# MCU.net
KiCad netlist of a schematic drawn in Altium Designer
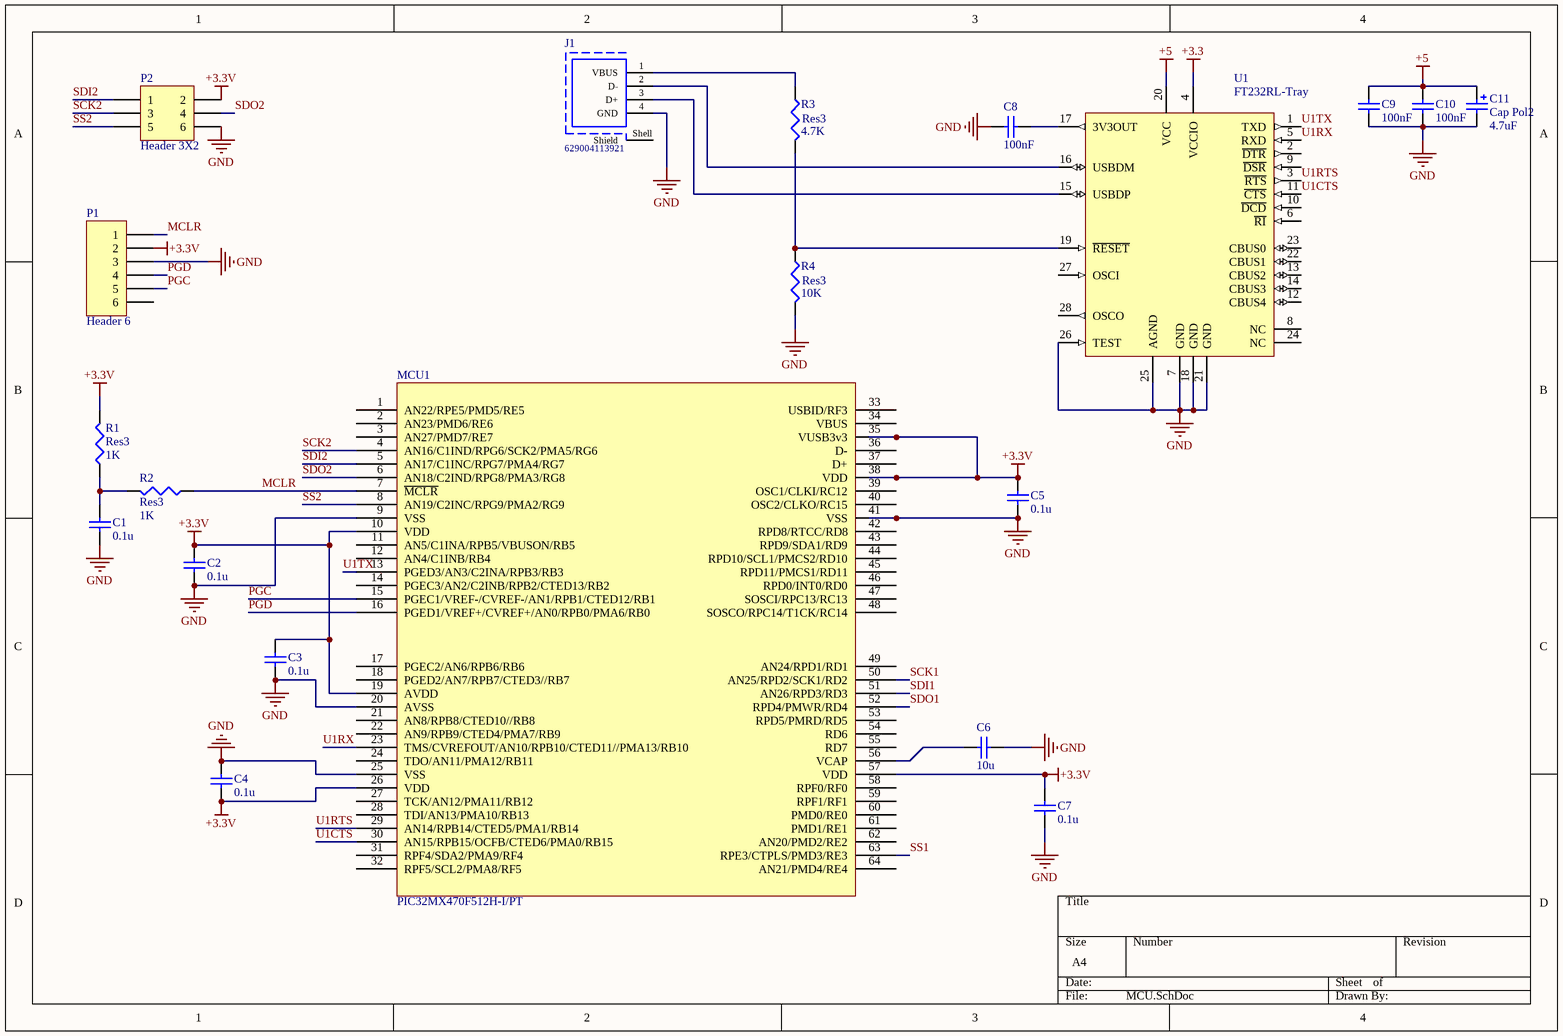
[diagram p0: MCU.SchDoc]

(export (version "E")
  (design (tool "Eeschema 10.0.6"))
  (components
    (comp (ref "C1")
      (value "0.1u")
      (footprint "0603")
      (description "CER 10UF 25V X8R 1210")
      (libsource (lib "LibSch") (part "C0603"))
    )
    (comp (ref "C2")
      (value "0.1u")
      (footprint "0603")
      (description "CER 10UF 25V X8R 1210")
      (libsource (lib "LibSch") (part "C0603"))
    )
    (comp (ref "C3")
      (value "0.1u")
      (footprint "0603")
      (description "CER 10UF 25V X8R 1210")
      (libsource (lib "LibSch") (part "C0603"))
    )
    (comp (ref "C4")
      (value "0.1u")
      (footprint "0603")
      (description "CER 10UF 25V X8R 1210")
      (libsource (lib "LibSch") (part "C0603"))
    )
    (comp (ref "C5")
      (value "0.1u")
      (footprint "0603")
      (description "CER 10UF 25V X8R 1210")
      (libsource (lib "LibSch") (part "C0603"))
    )
    (comp (ref "C6")
      (value "10u")
      (footprint "0603")
      (description "CER 10UF 25V X8R 1210")
      (libsource (lib "LibSch") (part "C0603"))
    )
    (comp (ref "C7")
      (value "0.1u")
      (footprint "0603")
      (description "CER 10UF 25V X8R 1210")
      (libsource (lib "LibSch") (part "C0603"))
    )
    (comp (ref "C8")
      (value "100nF")
      (footprint "0603")
      (description "CER 10UF 25V X8R 1210")
      (libsource (lib "LibSch") (part "C0603"))
    )
    (comp (ref "C9")
      (value "100nF")
      (footprint "0603")
      (description "CER 10UF 25V X8R 1210")
      (libsource (lib "LibSch") (part "C0603"))
    )
    (comp (ref "C10")
      (value "100nF")
      (footprint "0603")
      (description "CER 10UF 25V X8R 1210")
      (libsource (lib "LibSch") (part "C0603"))
    )
    (comp (ref "C11")
      (value "Cap Pol2")
      (footprint "POLAR0.8")
      (description "Polarized Capacitor (Axial)")
      (fields (field (name "ALTIUM_VALUE") "4.7uF") (field (name "PUBLISHER") "Altium Limited"))
      (libsource (lib "Miscellaneous Devices") (part "Cap Pol2"))
    )
    (comp (ref "J1")
      (value "629004113921")
      (footprint "629004113921")
      (description "USB 2.0 Type A Plug WR-COM, Horizontal, SMT, with Clips")
      (fields (field (name "MANUFACTURER") "Wurth Elektronik") (field (name "PUBLISHER") "WurthElektronik"))
      (libsource (lib "Altium Content Vault") (part "WE-USB-4-1SHLD"))
    )
    (comp (ref "MCU1")
      (value "PIC32MX470F512H-I/PT")
      (footprint "*QFP50P1200X1200X120-64N")
      (libsource (lib "MINTCustom") (part "PIC32MX470F512H-I/PT"))
    )
    (comp (ref "P1")
      (value "Header 6")
      (footprint "HDR1X6")
      (description "Header, 6-Pin")
      (fields (field (name "PUBLISHER") "Altium Limited"))
      (libsource (lib "Miscellaneous Connectors") (part "Header 6"))
    )
    (comp (ref "P2")
      (value "Header 3X2")
      (footprint "HDR2X3")
      (description "Header, 3-Pin, Dual row")
      (fields (field (name "PUBLISHER") "Altium Limited"))
      (libsource (lib "Miscellaneous Connectors") (part "Header 3X2"))
    )
    (comp (ref "R1")
      (value "Res3")
      (footprint "J1-0603")
      (description "Resistor")
      (fields (field (name "ALTIUM_VALUE") "1K") (field (name "PUBLISHER") "Altium Limited"))
      (libsource (lib "Miscellaneous Devices") (part "Res3"))
    )
    (comp (ref "R2")
      (value "Res3")
      (footprint "J1-0603")
      (description "Resistor")
      (fields (field (name "ALTIUM_VALUE") "1K") (field (name "PUBLISHER") "Altium Limited"))
      (libsource (lib "Miscellaneous Devices") (part "Res3"))
    )
    (comp (ref "R3")
      (value "Res3")
      (footprint "J1-0603")
      (description "Resistor")
      (fields (field (name "ALTIUM_VALUE") "4.7K") (field (name "PUBLISHER") "Altium Limited"))
      (libsource (lib "Miscellaneous Devices") (part "Res3"))
    )
    (comp (ref "R4")
      (value "Res3")
      (footprint "J1-0603")
      (description "Resistor")
      (fields (field (name "ALTIUM_VALUE") "10K") (field (name "PUBLISHER") "Altium Limited"))
      (libsource (lib "Miscellaneous Devices") (part "Res3"))
    )
    (comp (ref "U1")
      (value "FT232RL-Tray")
      (footprint "SSOP-28_L")
      (description "USB UART Asynchronous Serial Data Transfer Chip, SSOP-28, Tray")
      (libsource (lib "Altium Content Vault") (part "COM-UART-FT232R-IL28"))
    )
  )
  (nets
    (net (code "1") (name "+3.3") (class "Default")
      (node (ref "U1") (pin "4") (pinfunction "VCCIO_4") (pintype "power_in"))
    )
    (net (code "2") (name "+3.3V") (class "Default")
      (node (ref "C2") (pin "1") (pinfunction "1_1") (pintype "passive"))
      (node (ref "C3") (pin "1") (pinfunction "1_1") (pintype "passive"))
      (node (ref "C4") (pin "1") (pinfunction "1_1") (pintype "passive"))
      (node (ref "C5") (pin "1") (pinfunction "1_1") (pintype "passive"))
      (node (ref "C7") (pin "2") (pinfunction "2_2") (pintype "passive"))
      (node (ref "MCU1") (pin "10") (pinfunction "VDD_10") (pintype "passive"))
      (node (ref "MCU1") (pin "19") (pinfunction "AVDD_19") (pintype "passive"))
      (node (ref "MCU1") (pin "26") (pinfunction "VDD_26") (pintype "passive"))
      (node (ref "MCU1") (pin "35") (pinfunction "VUSB3v3_35") (pintype "passive"))
      (node (ref "MCU1") (pin "38") (pinfunction "VDD_38") (pintype "passive"))
      (node (ref "MCU1") (pin "57") (pinfunction "VDD_57") (pintype "passive"))
      (node (ref "P1") (pin "2") (pinfunction "2_2") (pintype "passive"))
      (node (ref "P2") (pin "2") (pinfunction "2_2") (pintype "passive"))
      (node (ref "R1") (pin "2") (pinfunction "2_2") (pintype "passive"))
    )
    (net (code "3") (name "+5") (class "Default")
      (node (ref "C10") (pin "1") (pinfunction "1_1") (pintype "passive"))
      (node (ref "C11") (pin "1") (pinfunction "1_1") (pintype "passive"))
      (node (ref "C9") (pin "1") (pinfunction "1_1") (pintype "passive"))
      (node (ref "U1") (pin "20") (pinfunction "VCC_20") (pintype "power_in"))
    )
    (net (code "4") (name "/MCLR") (class "Default")
      (node (ref "MCU1") (pin "7") (pinfunction "~{MCLR}_7") (pintype "passive"))
      (node (ref "P1") (pin "1") (pinfunction "1_1") (pintype "passive"))
      (node (ref "R2") (pin "1") (pinfunction "1_1") (pintype "passive"))
    )
    (net (code "5") (name "/PGC") (class "Default")
      (node (ref "MCU1") (pin "15") (pinfunction "PGEC1/VREF-/CVREF-/AN1/RPB1/CTED12/RB1_15") (pintype "passive"))
      (node (ref "P1") (pin "5") (pinfunction "5_5") (pintype "passive"))
    )
    (net (code "6") (name "/PGD") (class "Default")
      (node (ref "MCU1") (pin "16") (pinfunction "PGED1/VREF+/CVREF+/AN0/RPB0/PMA6/RB0_16") (pintype "passive"))
      (node (ref "P1") (pin "4") (pinfunction "4_4") (pintype "passive"))
    )
    (net (code "7") (name "/SCK1") (class "Default")
      (node (ref "MCU1") (pin "50") (pinfunction "AN25/RPD2/SCK1/RD2_50") (pintype "passive"))
    )
    (net (code "8") (name "/SCK2") (class "Default")
      (node (ref "MCU1") (pin "4") (pinfunction "AN16/C1IND/RPG6/SCK2/PMA5/RG6_4") (pintype "passive"))
      (node (ref "P2") (pin "3") (pinfunction "3_3") (pintype "passive"))
    )
    (net (code "9") (name "/SDI1") (class "Default")
      (node (ref "MCU1") (pin "51") (pinfunction "AN26/RPD3/RD3_51") (pintype "passive"))
    )
    (net (code "10") (name "/SDI2") (class "Default")
      (node (ref "MCU1") (pin "5") (pinfunction "AN17/C1INC/RPG7/PMA4/RG7_5") (pintype "passive"))
      (node (ref "P2") (pin "1") (pinfunction "1_1") (pintype "passive"))
    )
    (net (code "11") (name "/SDO1") (class "Default")
      (node (ref "MCU1") (pin "52") (pinfunction "RPD4/PMWR/RD4_52") (pintype "passive"))
    )
    (net (code "12") (name "/SDO2") (class "Default")
      (node (ref "MCU1") (pin "6") (pinfunction "AN18/C2IND/RPG8/PMA3/RG8_6") (pintype "passive"))
      (node (ref "P2") (pin "4") (pinfunction "4_4") (pintype "passive"))
    )
    (net (code "13") (name "/SS1") (class "Default")
      (node (ref "MCU1") (pin "63") (pinfunction "RPE3/CTPLS/PMD3/RE3_63") (pintype "passive"))
    )
    (net (code "14") (name "/SS2") (class "Default")
      (node (ref "MCU1") (pin "8") (pinfunction "AN19/C2INC/RPG9/PMA2/RG9_8") (pintype "passive"))
      (node (ref "P2") (pin "5") (pinfunction "5_5") (pintype "passive"))
    )
    (net (code "15") (name "/U1CTS") (class "Default")
      (node (ref "MCU1") (pin "30") (pinfunction "AN15/RPB15/OCFB/CTED6/PMA0/RB15_30") (pintype "passive"))
      (node (ref "U1") (pin "11") (pinfunction "~{CTS}_11") (pintype "input"))
    )
    (net (code "16") (name "/U1RTS") (class "Default")
      (node (ref "MCU1") (pin "29") (pinfunction "AN14/RPB14/CTED5/PMA1/RB14_29") (pintype "passive"))
      (node (ref "U1") (pin "3") (pinfunction "~{RTS}_3") (pintype "output"))
    )
    (net (code "17") (name "/U1RX") (class "Default")
      (node (ref "MCU1") (pin "23") (pinfunction "TMS/CVREFOUT/AN10/RPB10/CTED11//PMA13/RB10_23") (pintype "passive"))
      (node (ref "U1") (pin "5") (pinfunction "RXD_5") (pintype "input"))
    )
    (net (code "18") (name "/U1TX") (class "Default")
      (node (ref "MCU1") (pin "13") (pinfunction "PGED3/AN3/C2INA/RPB3/RB3_13") (pintype "passive"))
      (node (ref "U1") (pin "1") (pinfunction "TXD_1") (pintype "output"))
    )
    (net (code "19") (name "GND") (class "Default")
      (node (ref "C1") (pin "2") (pinfunction "2_2") (pintype "passive"))
      (node (ref "C10") (pin "2") (pinfunction "2_2") (pintype "passive"))
      (node (ref "C11") (pin "2") (pinfunction "2_2") (pintype "passive"))
      (node (ref "C2") (pin "2") (pinfunction "2_2") (pintype "passive"))
      (node (ref "C3") (pin "2") (pinfunction "2_2") (pintype "passive"))
      (node (ref "C4") (pin "2") (pinfunction "2_2") (pintype "passive"))
      (node (ref "C5") (pin "2") (pinfunction "2_2") (pintype "passive"))
      (node (ref "C6") (pin "1") (pinfunction "1_1") (pintype "passive"))
      (node (ref "C7") (pin "1") (pinfunction "1_1") (pintype "passive"))
      (node (ref "C8") (pin "2") (pinfunction "2_2") (pintype "passive"))
      (node (ref "C9") (pin "2") (pinfunction "2_2") (pintype "passive"))
      (node (ref "J1") (pin "4") (pinfunction "GND_4") (pintype "passive"))
      (node (ref "MCU1") (pin "20") (pinfunction "AVSS_20") (pintype "passive"))
      (node (ref "MCU1") (pin "25") (pinfunction "VSS_25") (pintype "passive"))
      (node (ref "MCU1") (pin "41") (pinfunction "VSS_41") (pintype "passive"))
      (node (ref "MCU1") (pin "9") (pinfunction "VSS_9") (pintype "passive"))
      (node (ref "P1") (pin "3") (pinfunction "3_3") (pintype "passive"))
      (node (ref "P2") (pin "6") (pinfunction "6_6") (pintype "passive"))
      (node (ref "R4") (pin "2") (pinfunction "2_2") (pintype "passive"))
      (node (ref "U1") (pin "18") (pinfunction "GND_18") (pintype "power_in"))
      (node (ref "U1") (pin "21") (pinfunction "GND_21") (pintype "power_in"))
      (node (ref "U1") (pin "25") (pinfunction "AGND_25") (pintype "power_in"))
      (node (ref "U1") (pin "26") (pinfunction "TEST_26") (pintype "input"))
      (node (ref "U1") (pin "7") (pinfunction "GND_7") (pintype "power_in"))
    )
    (net (code "20") (name "Net-(C1-Pad1)") (class "Default")
      (node (ref "C1") (pin "1") (pinfunction "1_1") (pintype "passive"))
      (node (ref "R1") (pin "1") (pinfunction "1_1") (pintype "passive"))
      (node (ref "R2") (pin "2") (pinfunction "2_2") (pintype "passive"))
    )
    (net (code "21") (name "Net-(J1-D+)") (class "Default")
      (node (ref "J1") (pin "3") (pinfunction "D+_3") (pintype "passive"))
      (node (ref "U1") (pin "15") (pinfunction "USBDP_15") (pintype "bidirectional"))
    )
    (net (code "22") (name "Net-(J1-D-)") (class "Default")
      (node (ref "J1") (pin "2") (pinfunction "D-_2") (pintype "passive"))
      (node (ref "U1") (pin "16") (pinfunction "USBDM_16") (pintype "bidirectional"))
    )
    (net (code "23") (name "Net-(J1-VBUS)") (class "Default")
      (node (ref "J1") (pin "1") (pinfunction "VBUS_1") (pintype "passive"))
      (node (ref "R3") (pin "1") (pinfunction "1_1") (pintype "passive"))
    )
    (net (code "24") (name "Net-(MCU1-VCAP)") (class "Default")
      (node (ref "C6") (pin "2") (pinfunction "2_2") (pintype "passive"))
      (node (ref "MCU1") (pin "56") (pinfunction "VCAP_56") (pintype "passive"))
    )
    (net (code "25") (name "Net-(U1-3V3OUT)") (class "Default")
      (node (ref "C8") (pin "1") (pinfunction "1_1") (pintype "passive"))
      (node (ref "U1") (pin "17") (pinfunction "3V3OUT_17") (pintype "output"))
    )
    (net (code "26") (name "Net-(U1-~{RESET})") (class "Default")
      (node (ref "R3") (pin "2") (pinfunction "2_2") (pintype "passive"))
      (node (ref "R4") (pin "1") (pinfunction "1_1") (pintype "passive"))
      (node (ref "U1") (pin "19") (pinfunction "~{RESET}_19") (pintype "input"))
    )
    (net (code "27") (name "unconnected-(J1-Shield-PadShell)") (class "Default")
      (node (ref "J1") (pin "Shell") (pinfunction "Shield_Shell") (pintype "passive"))
    )
    (net (code "28") (name "unconnected-(MCU1-AN4{slash}C1INB{slash}RB4-Pad12)") (class "Default")
      (node (ref "MCU1") (pin "12") (pinfunction "AN4/C1INB/RB4_12") (pintype "passive"))
    )
    (net (code "29") (name "unconnected-(MCU1-AN5{slash}C1INA{slash}RPB5{slash}VBUSON{slash}RB5-Pad11)") (class "Default")
      (node (ref "MCU1") (pin "11") (pinfunction "AN5/C1INA/RPB5/VBUSON/RB5_11") (pintype "passive"))
    )
    (net (code "30") (name "unconnected-(MCU1-AN8{slash}RPB8{slash}CTED10{slash}{slash}RB8-Pad21)") (class "Default")
      (node (ref "MCU1") (pin "21") (pinfunction "AN8/RPB8/CTED10//RB8_21") (pintype "passive"))
    )
    (net (code "31") (name "unconnected-(MCU1-AN9{slash}RPB9{slash}CTED4{slash}PMA7{slash}RB9-Pad22)") (class "Default")
      (node (ref "MCU1") (pin "22") (pinfunction "AN9/RPB9/CTED4/PMA7/RB9_22") (pintype "passive"))
    )
    (net (code "32") (name "unconnected-(MCU1-AN20{slash}PMD2{slash}RE2-Pad62)") (class "Default")
      (node (ref "MCU1") (pin "62") (pinfunction "AN20/PMD2/RE2_62") (pintype "passive"))
    )
    (net (code "33") (name "unconnected-(MCU1-AN21{slash}PMD4{slash}RE4-Pad64)") (class "Default")
      (node (ref "MCU1") (pin "64") (pinfunction "AN21/PMD4/RE4_64") (pintype "passive"))
    )
    (net (code "34") (name "unconnected-(MCU1-AN22{slash}RPE5{slash}PMD5{slash}RE5-Pad1)") (class "Default")
      (node (ref "MCU1") (pin "1") (pinfunction "AN22/RPE5/PMD5/RE5_1") (pintype "passive"))
    )
    (net (code "35") (name "unconnected-(MCU1-AN23{slash}PMD6{slash}RE6-Pad2)") (class "Default")
      (node (ref "MCU1") (pin "2") (pinfunction "AN23/PMD6/RE6_2") (pintype "passive"))
    )
    (net (code "36") (name "unconnected-(MCU1-AN27{slash}PMD7{slash}RE7-Pad3)") (class "Default")
      (node (ref "MCU1") (pin "3") (pinfunction "AN27/PMD7/RE7_3") (pintype "passive"))
    )
    (net (code "37") (name "unconnected-(MCU1-D+-Pad37)") (class "Default")
      (node (ref "MCU1") (pin "37") (pinfunction "D+_37") (pintype "passive"))
    )
    (net (code "38") (name "unconnected-(MCU1-D--Pad36)") (class "Default")
      (node (ref "MCU1") (pin "36") (pinfunction "D-_36") (pintype "passive"))
    )
    (net (code "39") (name "unconnected-(MCU1-OSC1{slash}CLKI{slash}RC12-Pad39)") (class "Default")
      (node (ref "MCU1") (pin "39") (pinfunction "OSC1/CLKI/RC12_39") (pintype "passive"))
    )
    (net (code "40") (name "unconnected-(MCU1-OSC2{slash}CLKO{slash}RC15-Pad40)") (class "Default")
      (node (ref "MCU1") (pin "40") (pinfunction "OSC2/CLKO/RC15_40") (pintype "passive"))
    )
    (net (code "41") (name "unconnected-(MCU1-PGEC2{slash}AN6{slash}RPB6{slash}RB6-Pad17)") (class "Default")
      (node (ref "MCU1") (pin "17") (pinfunction "PGEC2/AN6/RPB6/RB6_17") (pintype "passive"))
    )
    (net (code "42") (name "unconnected-(MCU1-PGEC3{slash}AN2{slash}C2INB{slash}RPB2{slash}CTED13{slash}RB2-Pad14)") (class "Default")
      (node (ref "MCU1") (pin "14") (pinfunction "PGEC3/AN2/C2INB/RPB2/CTED13/RB2_14") (pintype "passive"))
    )
    (net (code "43") (name "unconnected-(MCU1-PGED2{slash}AN7{slash}RPB7{slash}CTED3{slash}{slash}RB7-Pad18)") (class "Default")
      (node (ref "MCU1") (pin "18") (pinfunction "PGED2/AN7/RPB7/CTED3//RB7_18") (pintype "passive"))
    )
    (net (code "44") (name "unconnected-(MCU1-PMD0{slash}RE0-Pad60)") (class "Default")
      (node (ref "MCU1") (pin "60") (pinfunction "PMD0/RE0_60") (pintype "passive"))
    )
    (net (code "45") (name "unconnected-(MCU1-PMD1{slash}RE1-Pad61)") (class "Default")
      (node (ref "MCU1") (pin "61") (pinfunction "PMD1/RE1_61") (pintype "passive"))
    )
    (net (code "46") (name "unconnected-(MCU1-RD6-Pad54)") (class "Default")
      (node (ref "MCU1") (pin "54") (pinfunction "RD6_54") (pintype "passive"))
    )
    (net (code "47") (name "unconnected-(MCU1-RD7-Pad55)") (class "Default")
      (node (ref "MCU1") (pin "55") (pinfunction "RD7_55") (pintype "passive"))
    )
    (net (code "48") (name "unconnected-(MCU1-RPD0{slash}INT0{slash}RD0-Pad46)") (class "Default")
      (node (ref "MCU1") (pin "46") (pinfunction "RPD0/INT0/RD0_46") (pintype "passive"))
    )
    (net (code "49") (name "unconnected-(MCU1-RPD5{slash}PMRD{slash}RD5-Pad53)") (class "Default")
      (node (ref "MCU1") (pin "53") (pinfunction "RPD5/PMRD/RD5_53") (pintype "passive"))
    )
    (net (code "50") (name "unconnected-(MCU1-RPD8{slash}RTCC{slash}RD8-Pad42)") (class "Default")
      (node (ref "MCU1") (pin "42") (pinfunction "RPD8/RTCC/RD8_42") (pintype "passive"))
    )
    (net (code "51") (name "unconnected-(MCU1-RPD9{slash}SDA1{slash}RD9-Pad43)") (class "Default")
      (node (ref "MCU1") (pin "43") (pinfunction "RPD9/SDA1/RD9_43") (pintype "passive"))
    )
    (net (code "52") (name "unconnected-(MCU1-RPD11{slash}PMCS1{slash}RD11-Pad45)") (class "Default")
      (node (ref "MCU1") (pin "45") (pinfunction "RPD11/PMCS1/RD11_45") (pintype "passive"))
    )
    (net (code "53") (name "unconnected-(MCU1-RPF1{slash}RF1-Pad59)") (class "Default")
      (node (ref "MCU1") (pin "59") (pinfunction "RPF1/RF1_59") (pintype "passive"))
    )
    (net (code "54") (name "unconnected-(MCU1-RPF4{slash}SDA2{slash}PMA9{slash}RF4-Pad31)") (class "Default")
      (node (ref "MCU1") (pin "31") (pinfunction "RPF4/SDA2/PMA9/RF4_31") (pintype "passive"))
    )
    (net (code "55") (name "unconnected-(MCU1-RPF5{slash}SCL2{slash}PMA8{slash}RF5-Pad32)") (class "Default")
      (node (ref "MCU1") (pin "32") (pinfunction "RPF5/SCL2/PMA8/RF5_32") (pintype "passive"))
    )
    (net (code "56") (name "unconnected-(MCU1-SOSCI{slash}RPC13{slash}RC13-Pad47)") (class "Default")
      (node (ref "MCU1") (pin "47") (pinfunction "SOSCI/RPC13/RC13_47") (pintype "passive"))
    )
    (net (code "57") (name "unconnected-(MCU1-SOSCO{slash}RPC14{slash}T1CK{slash}RC14-Pad48)") (class "Default")
      (node (ref "MCU1") (pin "48") (pinfunction "SOSCO/RPC14/T1CK/RC14_48") (pintype "passive"))
    )
    (net (code "58") (name "unconnected-(MCU1-TCK{slash}AN12{slash}PMA11{slash}RB12-Pad27)") (class "Default")
      (node (ref "MCU1") (pin "27") (pinfunction "TCK/AN12/PMA11/RB12_27") (pintype "passive"))
    )
    (net (code "59") (name "unconnected-(MCU1-TDI{slash}AN13{slash}PMA10{slash}RB13-Pad28)") (class "Default")
      (node (ref "MCU1") (pin "28") (pinfunction "TDI/AN13/PMA10/RB13_28") (pintype "passive"))
    )
    (net (code "60") (name "unconnected-(MCU1-TDO{slash}AN11{slash}PMA12{slash}RB11-Pad24)") (class "Default")
      (node (ref "MCU1") (pin "24") (pinfunction "TDO/AN11/PMA12/RB11_24") (pintype "passive"))
    )
    (net (code "61") (name "unconnected-(MCU1-USBID{slash}RF3-Pad33)") (class "Default")
      (node (ref "MCU1") (pin "33") (pinfunction "USBID/RF3_33") (pintype "passive"))
    )
    (net (code "62") (name "unconnected-(MCU1-VBUS-Pad34)") (class "Default")
      (node (ref "MCU1") (pin "34") (pinfunction "VBUS_34") (pintype "passive"))
    )
    (net (code "63") (name "unconnected-(MCU1-_AN24{slash}RPD1{slash}RD1-Pad49)") (class "Default")
      (node (ref "MCU1") (pin "49") (pinfunction "_AN24/RPD1/RD1_49") (pintype "passive"))
    )
    (net (code "64") (name "unconnected-(MCU1-_RPD10{slash}SCL1{slash}PMCS2{slash}RD10-Pad44)") (class "Default")
      (node (ref "MCU1") (pin "44") (pinfunction "_RPD10/SCL1/PMCS2/RD10_44") (pintype "passive"))
    )
    (net (code "65") (name "unconnected-(MCU1-_RPF0{slash}RF0-Pad58)") (class "Default")
      (node (ref "MCU1") (pin "58") (pinfunction "_RPF0/RF0_58") (pintype "passive"))
    )
    (net (code "66") (name "unconnected-(P1-Pad6)") (class "Default")
      (node (ref "P1") (pin "6") (pinfunction "6_6") (pintype "passive"))
    )
    (net (code "67") (name "unconnected-(U1-CBUS0-Pad23)") (class "Default")
      (node (ref "U1") (pin "23") (pinfunction "CBUS0_23") (pintype "bidirectional"))
    )
    (net (code "68") (name "unconnected-(U1-CBUS1-Pad22)") (class "Default")
      (node (ref "U1") (pin "22") (pinfunction "CBUS1_22") (pintype "bidirectional"))
    )
    (net (code "69") (name "unconnected-(U1-CBUS2-Pad13)") (class "Default")
      (node (ref "U1") (pin "13") (pinfunction "CBUS2_13") (pintype "bidirectional"))
    )
    (net (code "70") (name "unconnected-(U1-CBUS3-Pad14)") (class "Default")
      (node (ref "U1") (pin "14") (pinfunction "CBUS3_14") (pintype "bidirectional"))
    )
    (net (code "71") (name "unconnected-(U1-CBUS4-Pad12)") (class "Default")
      (node (ref "U1") (pin "12") (pinfunction "CBUS4_12") (pintype "bidirectional"))
    )
    (net (code "72") (name "unconnected-(U1-NC-Pad8)") (class "Default")
      (node (ref "U1") (pin "8") (pinfunction "NC_8") (pintype "passive"))
    )
    (net (code "73") (name "unconnected-(U1-NC-Pad24)") (class "Default")
      (node (ref "U1") (pin "24") (pinfunction "NC_24") (pintype "passive"))
    )
    (net (code "74") (name "unconnected-(U1-OSCI-Pad27)") (class "Default")
      (node (ref "U1") (pin "27") (pinfunction "OSCI_27") (pintype "input"))
    )
    (net (code "75") (name "unconnected-(U1-OSCO-Pad28)") (class "Default")
      (node (ref "U1") (pin "28") (pinfunction "OSCO_28") (pintype "output"))
    )
    (net (code "76") (name "unconnected-(U1-~{DCD}-Pad10)") (class "Default")
      (node (ref "U1") (pin "10") (pinfunction "~{DCD}_10") (pintype "input"))
    )
    (net (code "77") (name "unconnected-(U1-~{DSR}-Pad9)") (class "Default")
      (node (ref "U1") (pin "9") (pinfunction "~{DSR}_9") (pintype "input"))
    )
    (net (code "78") (name "unconnected-(U1-~{DTR}-Pad2)") (class "Default")
      (node (ref "U1") (pin "2") (pinfunction "~{DTR}_2") (pintype "output"))
    )
    (net (code "79") (name "unconnected-(U1-~{RI}-Pad6)") (class "Default")
      (node (ref "U1") (pin "6") (pinfunction "~{RI}_6") (pintype "input"))
    )
  )
)
